# RaspPiPSOC.net
KiCad netlist of a schematic drawn in EAGLE
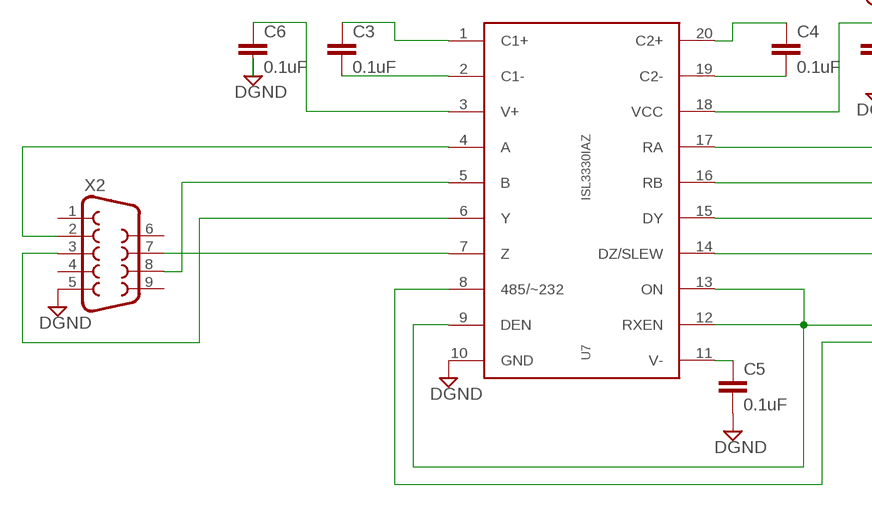
[diagram p0: schematic, sheet 1, part 1 of 2]
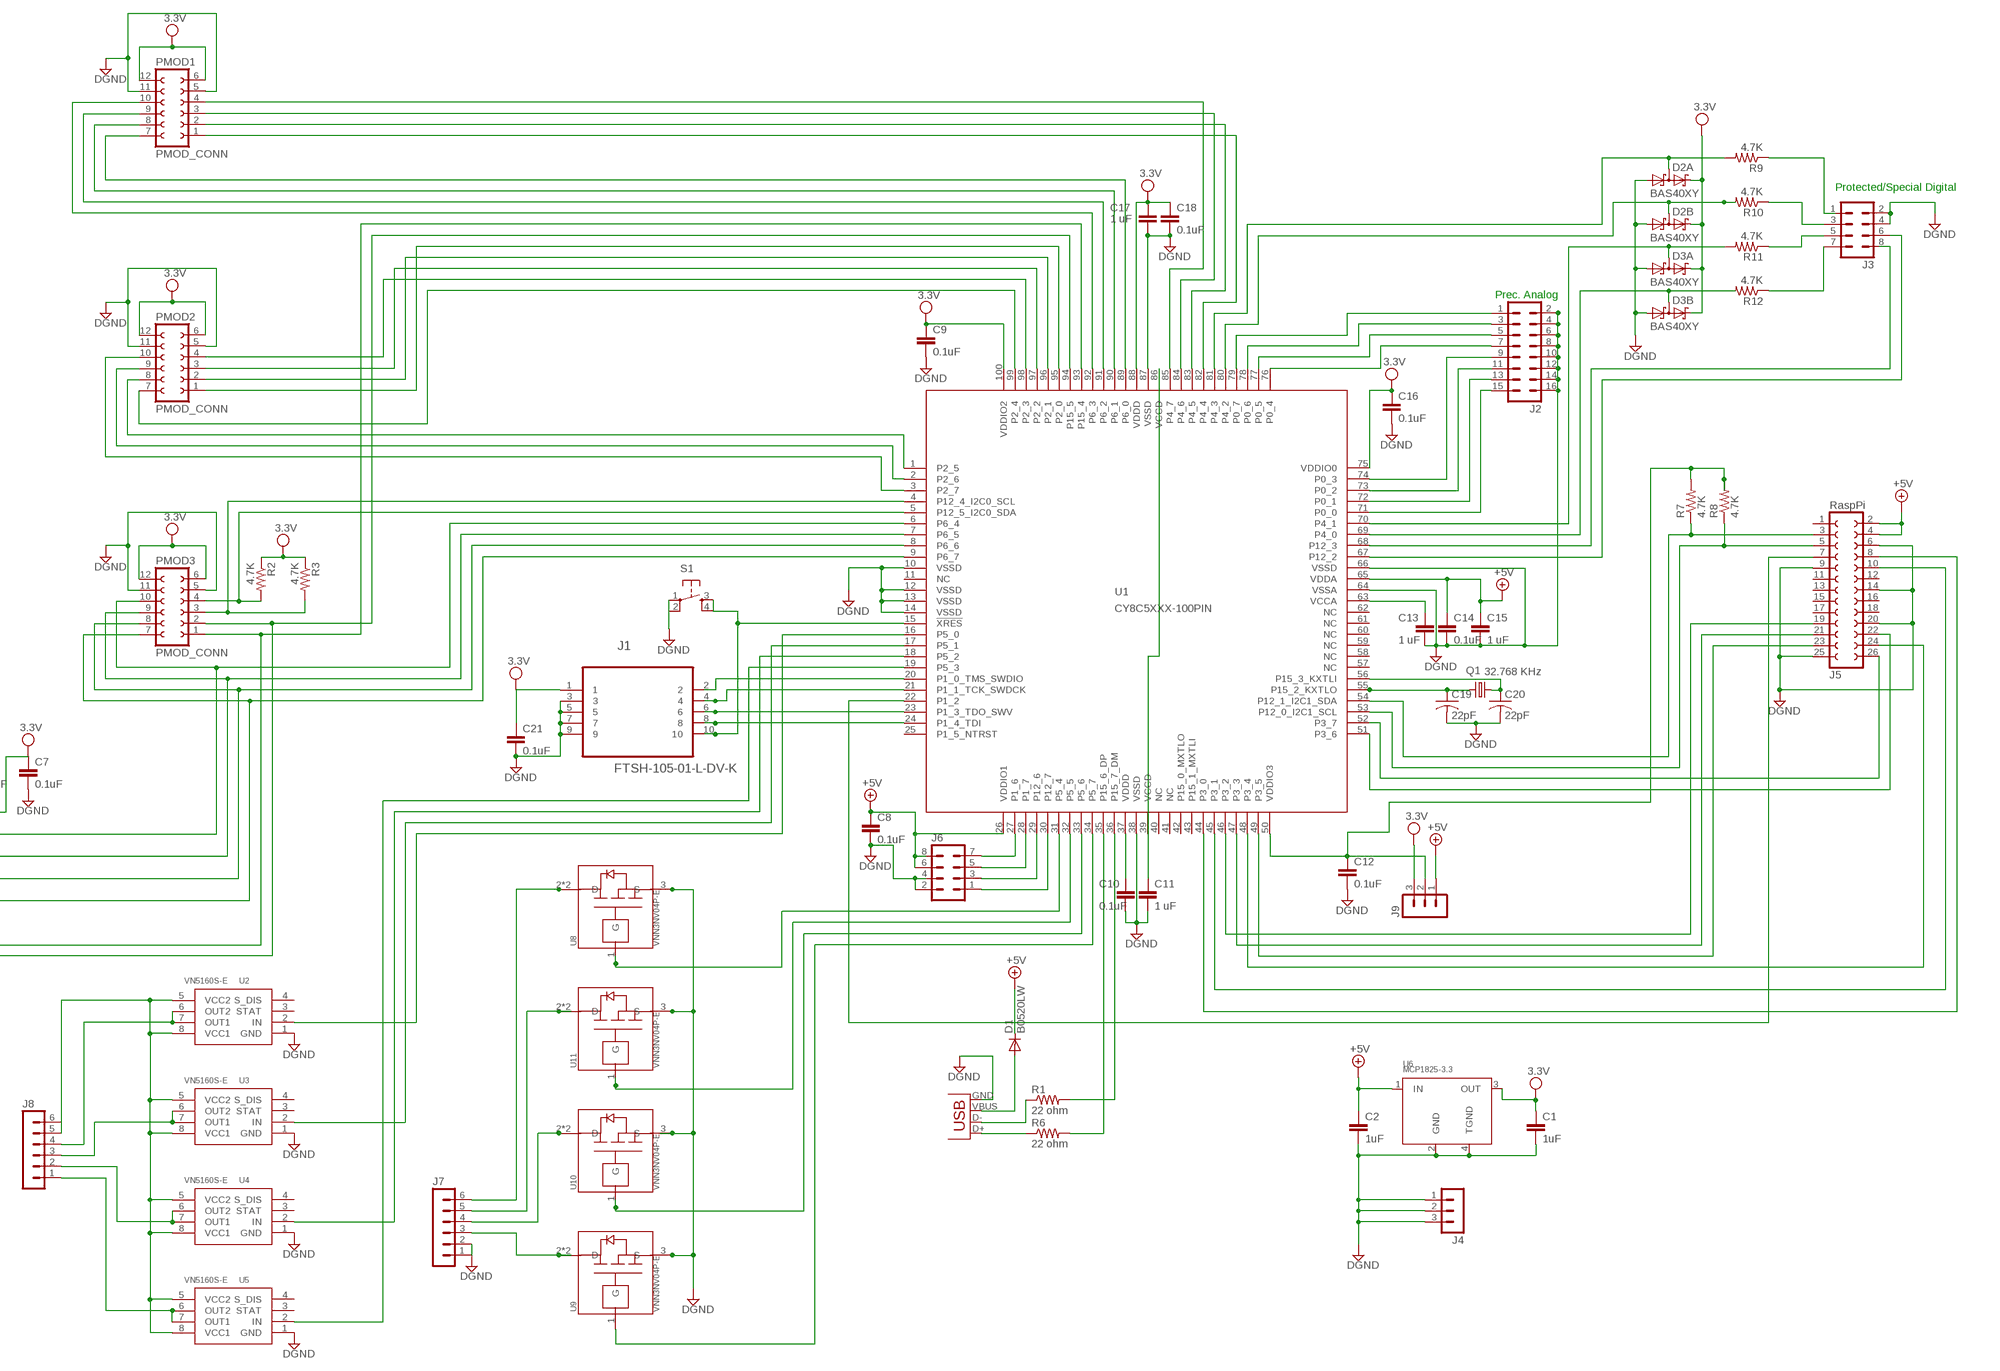
[diagram p1: schematic, sheet 1, part 2 of 2]

(export (version "E")
  (design (tool "Eeschema 10.0.6"))
  (components
    (comp (ref "C1")
      (value "1uF")
      (footprint "eagle-import:C0805")
      (libsource (lib "eagle-import") (part "resistor_C-EUC0805"))
    )
    (comp (ref "C2")
      (value "1uF")
      (footprint "eagle-import:C0805")
      (libsource (lib "eagle-import") (part "resistor_C-EUC0805"))
    )
    (comp (ref "C3")
      (value "0.1uF")
      (footprint "eagle-import:C0805")
      (libsource (lib "eagle-import") (part "C-EUC0805"))
    )
    (comp (ref "C4")
      (value "0.1uF")
      (footprint "eagle-import:C0805")
      (libsource (lib "eagle-import") (part "C-EUC0805"))
    )
    (comp (ref "C5")
      (value "0.1uF")
      (footprint "eagle-import:C0805")
      (libsource (lib "eagle-import") (part "C-EUC0805"))
    )
    (comp (ref "C6")
      (value "0.1uF")
      (footprint "eagle-import:C0805")
      (libsource (lib "eagle-import") (part "C-EUC0805"))
    )
    (comp (ref "C7")
      (value "0.1uF")
      (footprint "eagle-import:C0805")
      (libsource (lib "eagle-import") (part "C-EUC0805"))
    )
    (comp (ref "C8")
      (value "0.1uF")
      (footprint "eagle-import:C0805")
      (libsource (lib "eagle-import") (part "C-EUC0805"))
    )
    (comp (ref "C9")
      (value "0.1uF")
      (footprint "eagle-import:C0805")
      (libsource (lib "eagle-import") (part "C-EUC0805"))
    )
    (comp (ref "C10")
      (value "0.1uF")
      (footprint "eagle-import:C0805")
      (libsource (lib "eagle-import") (part "C-EUC0805"))
    )
    (comp (ref "C11")
      (value "1 uF")
      (footprint "eagle-import:C0805")
      (libsource (lib "eagle-import") (part "C-EUC0805"))
    )
    (comp (ref "C12")
      (value "0.1uF")
      (footprint "eagle-import:C0805")
      (libsource (lib "eagle-import") (part "C-EUC0805"))
    )
    (comp (ref "C13")
      (value "1 uF")
      (footprint "eagle-import:C0805")
      (libsource (lib "eagle-import") (part "C-EUC0805"))
    )
    (comp (ref "C14")
      (value "0.1uF")
      (footprint "eagle-import:C0805")
      (libsource (lib "eagle-import") (part "C-EUC0805"))
    )
    (comp (ref "C15")
      (value "1 uF")
      (footprint "eagle-import:C0805")
      (libsource (lib "eagle-import") (part "C-EUC0805"))
    )
    (comp (ref "C16")
      (value "0.1uF")
      (footprint "eagle-import:C0805")
      (libsource (lib "eagle-import") (part "C-EUC0805"))
    )
    (comp (ref "C17")
      (value "1 uF")
      (footprint "eagle-import:C0805")
      (libsource (lib "eagle-import") (part "C-EUC0805"))
    )
    (comp (ref "C18")
      (value "0.1uF")
      (footprint "eagle-import:C0805")
      (libsource (lib "eagle-import") (part "C-EUC0805"))
    )
    (comp (ref "C19")
      (value "22pF")
      (footprint "eagle-import:C0805")
      (libsource (lib "eagle-import") (part "C-USC0805"))
    )
    (comp (ref "C20")
      (value "22pF")
      (footprint "eagle-import:C0805")
      (libsource (lib "eagle-import") (part "C-USC0805"))
    )
    (comp (ref "C21")
      (value "0.1uF")
      (footprint "eagle-import:C0805")
      (libsource (lib "eagle-import") (part "C-EUC0805"))
    )
    (comp (ref "D1")
      (value "B0520LW")
      (footprint "eagle-import:SOD-123_MINI-SMA")
      (libsource (lib "eagle-import") (part "CGRM400-G3"))
    )
    (comp (ref "D2")
      (value "BAS40XY")
      (footprint "eagle-import:SOT363_PHILIPS")
      (libsource (lib "eagle-import") (part "BAS70XY"))
    )
    (comp (ref "D3")
      (value "BAS40XY")
      (footprint "eagle-import:SOT363_PHILIPS")
      (libsource (lib "eagle-import") (part "BAS70XY"))
    )
    (comp (ref "J1")
      (value "FTSH-105-01-L-DV-K")
      (footprint "eagle-import:SAMTEC_FTSH-105-01-L-DV-K")
      (libsource (lib "eagle-import") (part "FTSH-105-01-L-DV-K"))
    )
    (comp (ref "J2")
      (value "MA08-2")
      (footprint "eagle-import:MA08-2")
      (libsource (lib "eagle-import") (part "MA08-2"))
    )
    (comp (ref "J3")
      (value "MA04-2")
      (footprint "eagle-import:MA04-2")
      (libsource (lib "eagle-import") (part "MA04-2"))
    )
    (comp (ref "J4")
      (value "MA03-1")
      (footprint "eagle-import:MA03-1")
      (libsource (lib "eagle-import") (part "MA03-1"))
    )
    (comp (ref "J5")
      (value "RaspPi")
      (footprint "eagle-import:FE13-2")
      (libsource (lib "eagle-import") (part "FE13-2"))
    )
    (comp (ref "J6")
      (value "MA04-2")
      (footprint "eagle-import:MA04-2")
      (libsource (lib "eagle-import") (part "MA04-2"))
    )
    (comp (ref "J7")
      (value "MA06-1")
      (footprint "eagle-import:MA06-1")
      (libsource (lib "eagle-import") (part "MA06-1"))
    )
    (comp (ref "J8")
      (value "MA06-1")
      (footprint "eagle-import:MA06-1")
      (libsource (lib "eagle-import") (part "MA06-1"))
    )
    (comp (ref "J9")
      (value "MA03-1")
      (footprint "eagle-import:MA03-1")
      (libsource (lib "eagle-import") (part "MA03-1"))
    )
    (comp (ref "PMOD1")
      (value "PMOD_CONN")
      (footprint "eagle-import:PMOD_CONN")
      (libsource (lib "eagle-import") (part "PMOD_CONN"))
    )
    (comp (ref "PMOD2")
      (value "PMOD_CONN")
      (footprint "eagle-import:PMOD_CONN")
      (libsource (lib "eagle-import") (part "PMOD_CONN"))
    )
    (comp (ref "PMOD3")
      (value "PMOD_CONN")
      (footprint "eagle-import:PMOD_CONN")
      (libsource (lib "eagle-import") (part "PMOD_CONN"))
    )
    (comp (ref "Q1")
      (value "32.768 KHz")
      (footprint "eagle-import:TC26H")
      (libsource (lib "eagle-import") (part "CRYSTALTC26H"))
    )
    (comp (ref "R1")
      (value "22 ohm")
      (footprint "eagle-import:R0805")
      (libsource (lib "eagle-import") (part "R-US_R0805"))
    )
    (comp (ref "R2")
      (value "4.7K")
      (footprint "eagle-import:R0805")
      (libsource (lib "eagle-import") (part "R-US_R0805"))
    )
    (comp (ref "R3")
      (value "4.7K")
      (footprint "eagle-import:R0805")
      (libsource (lib "eagle-import") (part "R-US_R0805"))
    )
    (comp (ref "R6")
      (value "22 ohm")
      (footprint "eagle-import:R0805")
      (libsource (lib "eagle-import") (part "R-US_R0805"))
    )
    (comp (ref "R7")
      (value "4.7K")
      (footprint "eagle-import:R0805")
      (libsource (lib "eagle-import") (part "R-US_R0805"))
    )
    (comp (ref "R8")
      (value "4.7K")
      (footprint "eagle-import:R0805")
      (libsource (lib "eagle-import") (part "R-US_R0805"))
    )
    (comp (ref "R9")
      (value "4.7K")
      (footprint "eagle-import:R0805")
      (libsource (lib "eagle-import") (part "R-US_R0805"))
    )
    (comp (ref "R10")
      (value "4.7K")
      (footprint "eagle-import:R0805")
      (libsource (lib "eagle-import") (part "R-US_R0805"))
    )
    (comp (ref "R11")
      (value "4.7K")
      (footprint "eagle-import:R0805")
      (libsource (lib "eagle-import") (part "R-US_R0805"))
    )
    (comp (ref "R12")
      (value "4.7K")
      (footprint "eagle-import:R0805")
      (libsource (lib "eagle-import") (part "R-US_R0805"))
    )
    (comp (ref "S1")
      (value "TAC_SWITCHSMD")
      (footprint "eagle-import:TACTILE_SWITCH_SMD")
      (libsource (lib "eagle-import") (part "TAC_SWITCHSMD"))
    )
    (comp (ref "U1")
      (value "CY8C5XXX-100PIN")
      (footprint "eagle-import:TQFP-14X14-100")
      (fields (field (name "MPN") "CY8C5588AXI-060"))
      (libsource (lib "eagle-import") (part "CY8C5XXX-100PIN"))
    )
    (comp (ref "U2")
      (value "VN5160S-E")
      (footprint "eagle-import:SOIC8")
      (libsource (lib "eagle-import") (part "VN5160S-E"))
    )
    (comp (ref "U3")
      (value "VN5160S-E")
      (footprint "eagle-import:SOIC8")
      (libsource (lib "eagle-import") (part "VN5160S-E"))
    )
    (comp (ref "U4")
      (value "VN5160S-E")
      (footprint "eagle-import:SOIC8")
      (libsource (lib "eagle-import") (part "VN5160S-E"))
    )
    (comp (ref "U5")
      (value "VN5160S-E")
      (footprint "eagle-import:SOIC8")
      (libsource (lib "eagle-import") (part "VN5160S-E"))
    )
    (comp (ref "U6")
      (value "MCP1825-3.3")
      (footprint "eagle-import:SOT223")
      (libsource (lib "eagle-import") (part "TC1262"))
    )
    (comp (ref "U7")
      (value "ISL3330IAZ")
      (footprint "eagle-import:SSOP20")
      (libsource (lib "eagle-import") (part "ISL3330IAZ"))
    )
    (comp (ref "U8")
      (value "VNN3NV04P-E")
      (footprint "eagle-import:SOT223")
      (libsource (lib "eagle-import") (part "VNN3NV04P-E"))
    )
    (comp (ref "U9")
      (value "VNN3NV04P-E")
      (footprint "eagle-import:SOT223")
      (libsource (lib "eagle-import") (part "VNN3NV04P-E"))
    )
    (comp (ref "U10")
      (value "VNN3NV04P-E")
      (footprint "eagle-import:SOT223")
      (libsource (lib "eagle-import") (part "VNN3NV04P-E"))
    )
    (comp (ref "U11")
      (value "VNN3NV04P-E")
      (footprint "eagle-import:SOT223")
      (libsource (lib "eagle-import") (part "VNN3NV04P-E"))
    )
    (comp (ref "X1")
      (value "USBSMD")
      (footprint "eagle-import:USB-MINIB")
      (libsource (lib "eagle-import") (part "USBSMD"))
    )
    (comp (ref "X2")
      (value "DB9")
      (footprint "eagle-import:DB9")
      (libsource (lib "eagle-import") (part "DB9"))
    )
  )
  (nets
    (net (code "1") (name "+5V") (class "Default")
      (node (ref "C14") (pin "1") (pinfunction "1_1") (pintype "passive"))
      (node (ref "C15") (pin "1") (pinfunction "1_1") (pintype "passive"))
      (node (ref "C2") (pin "1") (pinfunction "1_1") (pintype "passive"))
      (node (ref "C8") (pin "1") (pinfunction "1_1") (pintype "passive"))
      (node (ref "D1") (pin "C") (pinfunction "C_C") (pintype "passive"))
      (node (ref "J5") (pin "2") (pinfunction "2_2") (pintype "passive"))
      (node (ref "J5") (pin "4") (pinfunction "4_4") (pintype "passive"))
      (node (ref "J6") (pin "6") (pinfunction "6_6") (pintype "passive"))
      (node (ref "J6") (pin "8") (pinfunction "8_8") (pintype "passive"))
      (node (ref "J9") (pin "1") (pinfunction "1_1") (pintype "passive"))
      (node (ref "U1") (pin "26") (pinfunction "VDDIO1_26") (pintype "passive"))
      (node (ref "U1") (pin "65") (pinfunction "VDDA_65") (pintype "passive"))
      (node (ref "U6") (pin "1") (pinfunction "IN_1") (pintype "bidirectional"))
    )
    (net (code "2") (name "3.3V") (class "Default")
      (node (ref "C1") (pin "1") (pinfunction "1_1") (pintype "passive"))
      (node (ref "C16") (pin "1") (pinfunction "1_1") (pintype "passive"))
      (node (ref "C17") (pin "1") (pinfunction "1_1") (pintype "passive"))
      (node (ref "C18") (pin "1") (pinfunction "1_1") (pintype "passive"))
      (node (ref "C21") (pin "1") (pinfunction "1_1") (pintype "passive"))
      (node (ref "C7") (pin "1") (pinfunction "1_1") (pintype "passive"))
      (node (ref "C9") (pin "1") (pinfunction "1_1") (pintype "passive"))
      (node (ref "D2") (pin "2") (pinfunction "C2_2") (pintype "passive"))
      (node (ref "D2") (pin "5") (pinfunction "C2_5") (pintype "passive"))
      (node (ref "D3") (pin "2") (pinfunction "C2_2") (pintype "passive"))
      (node (ref "D3") (pin "5") (pinfunction "C2_5") (pintype "passive"))
      (node (ref "J1") (pin "1") (pinfunction "1_1") (pintype "passive"))
      (node (ref "J9") (pin "3") (pinfunction "3_3") (pintype "passive"))
      (node (ref "PMOD1") (pin "12") (pinfunction "12_12") (pintype "passive"))
      (node (ref "PMOD1") (pin "6") (pinfunction "6_6") (pintype "passive"))
      (node (ref "PMOD2") (pin "12") (pinfunction "12_12") (pintype "passive"))
      (node (ref "PMOD2") (pin "6") (pinfunction "6_6") (pintype "passive"))
      (node (ref "PMOD3") (pin "12") (pinfunction "12_12") (pintype "passive"))
      (node (ref "PMOD3") (pin "6") (pinfunction "6_6") (pintype "passive"))
      (node (ref "R2") (pin "1") (pinfunction "1_1") (pintype "passive"))
      (node (ref "R3") (pin "1") (pinfunction "1_1") (pintype "passive"))
      (node (ref "U1") (pin "100") (pinfunction "VDDIO2_100") (pintype "passive"))
      (node (ref "U1") (pin "75") (pinfunction "VDDIO0_75") (pintype "passive"))
      (node (ref "U1") (pin "88") (pinfunction "VDDD_88") (pintype "passive"))
      (node (ref "U6") (pin "3") (pinfunction "OUT_3") (pintype "bidirectional"))
      (node (ref "U7") (pin "18") (pinfunction "VCC_18") (pintype "power_in"))
    )
    (net (code "3") (name "DGND") (class "Default")
      (node (ref "C1") (pin "2") (pinfunction "2_2") (pintype "passive"))
      (node (ref "C10") (pin "2") (pinfunction "2_2") (pintype "passive"))
      (node (ref "C11") (pin "2") (pinfunction "2_2") (pintype "passive"))
      (node (ref "C12") (pin "2") (pinfunction "2_2") (pintype "passive"))
      (node (ref "C13") (pin "2") (pinfunction "2_2") (pintype "passive"))
      (node (ref "C14") (pin "2") (pinfunction "2_2") (pintype "passive"))
      (node (ref "C15") (pin "2") (pinfunction "2_2") (pintype "passive"))
      (node (ref "C16") (pin "2") (pinfunction "2_2") (pintype "passive"))
      (node (ref "C17") (pin "2") (pinfunction "2_2") (pintype "passive"))
      (node (ref "C18") (pin "2") (pinfunction "2_2") (pintype "passive"))
      (node (ref "C19") (pin "2") (pinfunction "2_2") (pintype "passive"))
      (node (ref "C2") (pin "2") (pinfunction "2_2") (pintype "passive"))
      (node (ref "C20") (pin "2") (pinfunction "2_2") (pintype "passive"))
      (node (ref "C21") (pin "2") (pinfunction "2_2") (pintype "passive"))
      (node (ref "C5") (pin "2") (pinfunction "2_2") (pintype "passive"))
      (node (ref "C6") (pin "2") (pinfunction "2_2") (pintype "passive"))
      (node (ref "C7") (pin "2") (pinfunction "2_2") (pintype "passive"))
      (node (ref "C8") (pin "2") (pinfunction "2_2") (pintype "passive"))
      (node (ref "C9") (pin "2") (pinfunction "2_2") (pintype "passive"))
      (node (ref "D2") (pin "1") (pinfunction "A1_1") (pintype "passive"))
      (node (ref "D2") (pin "4") (pinfunction "A1_4") (pintype "passive"))
      (node (ref "D3") (pin "1") (pinfunction "A1_1") (pintype "passive"))
      (node (ref "D3") (pin "4") (pinfunction "A1_4") (pintype "passive"))
      (node (ref "J1") (pin "3") (pinfunction "3_3") (pintype "passive"))
      (node (ref "J1") (pin "5") (pinfunction "5_5") (pintype "passive"))
      (node (ref "J1") (pin "7") (pinfunction "7_7") (pintype "passive"))
      (node (ref "J1") (pin "9") (pinfunction "9_9") (pintype "passive"))
      (node (ref "J2") (pin "10") (pinfunction "10_10") (pintype "passive"))
      (node (ref "J2") (pin "12") (pinfunction "12_12") (pintype "passive"))
      (node (ref "J2") (pin "14") (pinfunction "14_14") (pintype "passive"))
      (node (ref "J2") (pin "16") (pinfunction "16_16") (pintype "passive"))
      (node (ref "J2") (pin "2") (pinfunction "2_2") (pintype "passive"))
      (node (ref "J2") (pin "4") (pinfunction "4_4") (pintype "passive"))
      (node (ref "J2") (pin "6") (pinfunction "6_6") (pintype "passive"))
      (node (ref "J2") (pin "8") (pinfunction "8_8") (pintype "passive"))
      (node (ref "J3") (pin "2") (pinfunction "2_2") (pintype "passive"))
      (node (ref "J3") (pin "4") (pinfunction "4_4") (pintype "passive"))
      (node (ref "J4") (pin "1") (pinfunction "1_1") (pintype "passive"))
      (node (ref "J4") (pin "2") (pinfunction "2_2") (pintype "passive"))
      (node (ref "J4") (pin "3") (pinfunction "3_3") (pintype "passive"))
      (node (ref "J5") (pin "14") (pinfunction "14_14") (pintype "passive"))
      (node (ref "J5") (pin "20") (pinfunction "20_20") (pintype "passive"))
      (node (ref "J5") (pin "25") (pinfunction "25_25") (pintype "passive"))
      (node (ref "J5") (pin "6") (pinfunction "6_6") (pintype "passive"))
      (node (ref "J5") (pin "9") (pinfunction "9_9") (pintype "passive"))
      (node (ref "J6") (pin "2") (pinfunction "2_2") (pintype "passive"))
      (node (ref "J6") (pin "4") (pinfunction "4_4") (pintype "passive"))
      (node (ref "J7") (pin "1") (pinfunction "1_1") (pintype "passive"))
      (node (ref "J7") (pin "2") (pinfunction "2_2") (pintype "passive"))
      (node (ref "PMOD1") (pin "11") (pinfunction "11_11") (pintype "passive"))
      (node (ref "PMOD1") (pin "5") (pinfunction "5_5") (pintype "passive"))
      (node (ref "PMOD2") (pin "11") (pinfunction "11_11") (pintype "passive"))
      (node (ref "PMOD2") (pin "5") (pinfunction "5_5") (pintype "passive"))
      (node (ref "PMOD3") (pin "11") (pinfunction "11_11") (pintype "passive"))
      (node (ref "PMOD3") (pin "5") (pinfunction "5_5") (pintype "passive"))
      (node (ref "S1") (pin "1") (pinfunction "1_1") (pintype "passive"))
      (node (ref "S1") (pin "2") (pinfunction "2_2") (pintype "passive"))
      (node (ref "U1") (pin "10") (pinfunction "VSSD_10") (pintype "passive"))
      (node (ref "U1") (pin "12") (pinfunction "VSSD_12") (pintype "passive"))
      (node (ref "U1") (pin "13") (pinfunction "VSSD_13") (pintype "passive"))
      (node (ref "U1") (pin "14") (pinfunction "VSSD_14") (pintype "passive"))
      (node (ref "U1") (pin "38") (pinfunction "VSSD_38") (pintype "passive"))
      (node (ref "U1") (pin "64") (pinfunction "VSSA_64") (pintype "passive"))
      (node (ref "U1") (pin "66") (pinfunction "VSSD_66") (pintype "passive"))
      (node (ref "U1") (pin "87") (pinfunction "VSSD_87") (pintype "passive"))
      (node (ref "U10") (pin "3") (pinfunction "S_3") (pintype "bidirectional"))
      (node (ref "U11") (pin "3") (pinfunction "S_3") (pintype "bidirectional"))
      (node (ref "U2") (pin "1") (pinfunction "GND_1") (pintype "power_in"))
      (node (ref "U3") (pin "1") (pinfunction "GND_1") (pintype "power_in"))
      (node (ref "U4") (pin "1") (pinfunction "GND_1") (pintype "power_in"))
      (node (ref "U5") (pin "1") (pinfunction "GND_1") (pintype "power_in"))
      (node (ref "U6") (pin "2") (pinfunction "GND_2") (pintype "bidirectional"))
      (node (ref "U6") (pin "4") (pinfunction "TGND_4") (pintype "bidirectional"))
      (node (ref "U7") (pin "10") (pinfunction "GND_10") (pintype "power_in"))
      (node (ref "U8") (pin "3") (pinfunction "S_3") (pintype "bidirectional"))
      (node (ref "U9") (pin "3") (pinfunction "S_3") (pintype "bidirectional"))
      (node (ref "X1") (pin "GND") (pinfunction "GND_GND") (pintype "bidirectional"))
      (node (ref "X2") (pin "5") (pinfunction "5_5") (pintype "passive"))
    )
    (net (code "4") (name "Net-(C10-Pad1)") (class "Default")
      (node (ref "C10") (pin "1") (pinfunction "1_1") (pintype "passive"))
      (node (ref "U1") (pin "37") (pinfunction "VDDD_37") (pintype "passive"))
    )
    (net (code "5") (name "Net-(C11-Pad1)") (class "Default")
      (node (ref "C11") (pin "1") (pinfunction "1_1") (pintype "passive"))
      (node (ref "U1") (pin "39") (pinfunction "VCCD_39") (pintype "passive"))
      (node (ref "U1") (pin "86") (pinfunction "VCCD_86") (pintype "passive"))
    )
    (net (code "6") (name "Net-(D1-PadA)") (class "Default")
      (node (ref "D1") (pin "A") (pinfunction "A_A") (pintype "passive"))
      (node (ref "X1") (pin "VBUS") (pinfunction "VBUS_VBUS") (pintype "bidirectional"))
    )
    (net (code "7") (name "Net-(D2A-C1A2)") (class "Default")
      (node (ref "D2") (pin "6") (pinfunction "C1A2_6") (pintype "passive"))
      (node (ref "R9") (pin "2") (pinfunction "2_2") (pintype "passive"))
      (node (ref "U1") (pin "81") (pinfunction "P4_3_81") (pintype "passive"))
    )
    (net (code "8") (name "Net-(D2B-C1A2)") (class "Default")
      (node (ref "D2") (pin "3") (pinfunction "C1A2_3") (pintype "passive"))
      (node (ref "R10") (pin "2") (pinfunction "2_2") (pintype "passive"))
      (node (ref "U1") (pin "80") (pinfunction "P4_2_80") (pintype "passive"))
    )
    (net (code "9") (name "Net-(D3A-C1A2)") (class "Default")
      (node (ref "D3") (pin "6") (pinfunction "C1A2_6") (pintype "passive"))
      (node (ref "R11") (pin "2") (pinfunction "2_2") (pintype "passive"))
      (node (ref "U1") (pin "70") (pinfunction "P4_1_70") (pintype "passive"))
    )
    (net (code "10") (name "Net-(D3B-C1A2)") (class "Default")
      (node (ref "D3") (pin "3") (pinfunction "C1A2_3") (pintype "passive"))
      (node (ref "R12") (pin "2") (pinfunction "2_2") (pintype "passive"))
      (node (ref "U1") (pin "69") (pinfunction "P4_0_69") (pintype "passive"))
    )
    (net (code "11") (name "Net-(J3-Pad1)") (class "Default")
      (node (ref "J3") (pin "1") (pinfunction "1_1") (pintype "passive"))
      (node (ref "R9") (pin "1") (pinfunction "1_1") (pintype "passive"))
    )
    (net (code "12") (name "Net-(J3-Pad3)") (class "Default")
      (node (ref "J3") (pin "3") (pinfunction "3_3") (pintype "passive"))
      (node (ref "R10") (pin "1") (pinfunction "1_1") (pintype "passive"))
    )
    (net (code "13") (name "Net-(J3-Pad5)") (class "Default")
      (node (ref "J3") (pin "5") (pinfunction "5_5") (pintype "passive"))
      (node (ref "R11") (pin "1") (pinfunction "1_1") (pintype "passive"))
    )
    (net (code "14") (name "Net-(J3-Pad7)") (class "Default")
      (node (ref "J3") (pin "7") (pinfunction "7_7") (pintype "passive"))
      (node (ref "R12") (pin "1") (pinfunction "1_1") (pintype "passive"))
    )
    (net (code "15") (name "Net-(J7-Pad3)") (class "Default")
      (node (ref "J7") (pin "3") (pinfunction "3_3") (pintype "passive"))
      (node (ref "U9") (pin "2") (pinfunction "D_2") (pintype "bidirectional"))
      (node (ref "U9") (pin "4") (pinfunction "D_4") (pintype "bidirectional"))
    )
    (net (code "16") (name "Net-(J7-Pad4)") (class "Default")
      (node (ref "J7") (pin "4") (pinfunction "4_4") (pintype "passive"))
      (node (ref "U10") (pin "2") (pinfunction "D_2") (pintype "bidirectional"))
      (node (ref "U10") (pin "4") (pinfunction "D_4") (pintype "bidirectional"))
    )
    (net (code "17") (name "Net-(J7-Pad5)") (class "Default")
      (node (ref "J7") (pin "5") (pinfunction "5_5") (pintype "passive"))
      (node (ref "U11") (pin "2") (pinfunction "D_2") (pintype "bidirectional"))
      (node (ref "U11") (pin "4") (pinfunction "D_4") (pintype "bidirectional"))
    )
    (net (code "18") (name "Net-(J7-Pad6)") (class "Default")
      (node (ref "J7") (pin "6") (pinfunction "6_6") (pintype "passive"))
      (node (ref "U8") (pin "2") (pinfunction "D_2") (pintype "bidirectional"))
      (node (ref "U8") (pin "4") (pinfunction "D_4") (pintype "bidirectional"))
    )
    (net (code "19") (name "Net-(R1-Pad1)") (class "Default")
      (node (ref "R1") (pin "1") (pinfunction "1_1") (pintype "passive"))
      (node (ref "X1") (pin "D-") (pinfunction "D-_D-") (pintype "bidirectional"))
    )
    (net (code "20") (name "Net-(R6-Pad1)") (class "Default")
      (node (ref "R6") (pin "1") (pinfunction "1_1") (pintype "passive"))
      (node (ref "X1") (pin "D+") (pinfunction "D+_D+") (pintype "bidirectional"))
    )
    (net (code "21") (name "Net-(U1-P0_0)") (class "Default")
      (node (ref "J2") (pin "15") (pinfunction "15_15") (pintype "passive"))
      (node (ref "U1") (pin "71") (pinfunction "P0_0_71") (pintype "passive"))
    )
    (net (code "22") (name "Net-(U1-P0_1)") (class "Default")
      (node (ref "J2") (pin "13") (pinfunction "13_13") (pintype "passive"))
      (node (ref "U1") (pin "72") (pinfunction "P0_1_72") (pintype "passive"))
    )
    (net (code "23") (name "Net-(U1-P0_2)") (class "Default")
      (node (ref "J2") (pin "11") (pinfunction "11_11") (pintype "passive"))
      (node (ref "U1") (pin "73") (pinfunction "P0_2_73") (pintype "passive"))
    )
    (net (code "24") (name "Net-(U1-P0_3)") (class "Default")
      (node (ref "J2") (pin "9") (pinfunction "9_9") (pintype "passive"))
      (node (ref "U1") (pin "74") (pinfunction "P0_3_74") (pintype "passive"))
    )
    (net (code "25") (name "Net-(U1-P0_4)") (class "Default")
      (node (ref "J2") (pin "7") (pinfunction "7_7") (pintype "passive"))
      (node (ref "U1") (pin "76") (pinfunction "P0_4_76") (pintype "passive"))
    )
    (net (code "26") (name "Net-(U1-P0_5)") (class "Default")
      (node (ref "J2") (pin "5") (pinfunction "5_5") (pintype "passive"))
      (node (ref "U1") (pin "77") (pinfunction "P0_5_77") (pintype "passive"))
    )
    (net (code "27") (name "Net-(U1-P0_6)") (class "Default")
      (node (ref "J2") (pin "3") (pinfunction "3_3") (pintype "passive"))
      (node (ref "U1") (pin "78") (pinfunction "P0_6_78") (pintype "passive"))
    )
    (net (code "28") (name "Net-(U1-P0_7)") (class "Default")
      (node (ref "J2") (pin "1") (pinfunction "1_1") (pintype "passive"))
      (node (ref "U1") (pin "79") (pinfunction "P0_7_79") (pintype "passive"))
    )
    (net (code "29") (name "Net-(U1-P1_0_TMS_SWDIO)") (class "Default")
      (node (ref "J1") (pin "2") (pinfunction "2_2") (pintype "passive"))
      (node (ref "U1") (pin "20") (pinfunction "P1_0_TMS_SWDIO_20") (pintype "passive"))
    )
    (net (code "30") (name "Net-(U1-P1_1_TCK_SWDCK)") (class "Default")
      (node (ref "J1") (pin "4") (pinfunction "4_4") (pintype "passive"))
      (node (ref "U1") (pin "21") (pinfunction "P1_1_TCK_SWDCK_21") (pintype "passive"))
    )
    (net (code "31") (name "Net-(U1-P1_2)") (class "Default")
      (node (ref "J5") (pin "7") (pinfunction "7_7") (pintype "passive"))
      (node (ref "U1") (pin "22") (pinfunction "P1_2_22") (pintype "passive"))
    )
    (net (code "32") (name "Net-(U1-P1_3_TDO_SWV)") (class "Default")
      (node (ref "J1") (pin "6") (pinfunction "6_6") (pintype "passive"))
      (node (ref "U1") (pin "23") (pinfunction "P1_3_TDO_SWV_23") (pintype "passive"))
    )
    (net (code "33") (name "Net-(U1-P1_4_TDI)") (class "Default")
      (node (ref "J1") (pin "8") (pinfunction "8_8") (pintype "passive"))
      (node (ref "U1") (pin "24") (pinfunction "P1_4_TDI_24") (pintype "passive"))
    )
    (net (code "34") (name "Net-(U1-P1_6)") (class "Default")
      (node (ref "J6") (pin "7") (pinfunction "7_7") (pintype "passive"))
      (node (ref "U1") (pin "27") (pinfunction "P1_6_27") (pintype "passive"))
    )
    (net (code "35") (name "Net-(U1-P1_7)") (class "Default")
      (node (ref "J6") (pin "5") (pinfunction "5_5") (pintype "passive"))
      (node (ref "U1") (pin "28") (pinfunction "P1_7_28") (pintype "passive"))
    )
    (net (code "36") (name "Net-(U1-P2_0)") (class "Default")
      (node (ref "PMOD2") (pin "1") (pinfunction "1_1") (pintype "passive"))
      (node (ref "U1") (pin "95") (pinfunction "P2_0_95") (pintype "passive"))
    )
    (net (code "37") (name "Net-(U1-P2_1)") (class "Default")
      (node (ref "PMOD2") (pin "2") (pinfunction "2_2") (pintype "passive"))
      (node (ref "U1") (pin "96") (pinfunction "P2_1_96") (pintype "passive"))
    )
    (net (code "38") (name "Net-(U1-P2_2)") (class "Default")
      (node (ref "PMOD2") (pin "3") (pinfunction "3_3") (pintype "passive"))
      (node (ref "U1") (pin "97") (pinfunction "P2_2_97") (pintype "passive"))
    )
    (net (code "39") (name "Net-(U1-P2_3)") (class "Default")
      (node (ref "PMOD2") (pin "4") (pinfunction "4_4") (pintype "passive"))
      (node (ref "U1") (pin "98") (pinfunction "P2_3_98") (pintype "passive"))
    )
    (net (code "40") (name "Net-(U1-P2_4)") (class "Default")
      (node (ref "PMOD2") (pin "7") (pinfunction "7_7") (pintype "passive"))
      (node (ref "U1") (pin "99") (pinfunction "P2_4_99") (pintype "passive"))
    )
    (net (code "41") (name "Net-(U1-P2_5)") (class "Default")
      (node (ref "PMOD2") (pin "8") (pinfunction "8_8") (pintype "passive"))
      (node (ref "U1") (pin "1") (pinfunction "P2_5_1") (pintype "passive"))
    )
    (net (code "42") (name "Net-(U1-P2_6)") (class "Default")
      (node (ref "PMOD2") (pin "9") (pinfunction "9_9") (pintype "passive"))
      (node (ref "U1") (pin "2") (pinfunction "P2_6_2") (pintype "passive"))
    )
    (net (code "43") (name "Net-(U1-P2_7)") (class "Default")
      (node (ref "PMOD2") (pin "10") (pinfunction "10_10") (pintype "passive"))
      (node (ref "U1") (pin "3") (pinfunction "P2_7_3") (pintype "passive"))
    )
    (net (code "44") (name "Net-(U1-P3_0)") (class "Default")
      (node (ref "J5") (pin "8") (pinfunction "8_8") (pintype "passive"))
      (node (ref "U1") (pin "44") (pinfunction "P3_0_44") (pintype "passive"))
    )
    (net (code "45") (name "Net-(U1-P3_1)") (class "Default")
      (node (ref "J5") (pin "10") (pinfunction "10_10") (pintype "passive"))
      (node (ref "U1") (pin "45") (pinfunction "P3_1_45") (pintype "passive"))
    )
    (net (code "46") (name "Net-(U1-P3_2)") (class "Default")
      (node (ref "J5") (pin "19") (pinfunction "19_19") (pintype "passive"))
      (node (ref "U1") (pin "46") (pinfunction "P3_2_46") (pintype "passive"))
    )
    (net (code "47") (name "Net-(U1-P3_3)") (class "Default")
      (node (ref "J5") (pin "21") (pinfunction "21_21") (pintype "passive"))
      (node (ref "U1") (pin "47") (pinfunction "P3_3_47") (pintype "passive"))
    )
    (net (code "48") (name "Net-(U1-P3_4)") (class "Default")
      (node (ref "J5") (pin "24") (pinfunction "24_24") (pintype "passive"))
      (node (ref "U1") (pin "48") (pinfunction "P3_4_48") (pintype "passive"))
    )
    (net (code "49") (name "Net-(U1-P3_5)") (class "Default")
      (node (ref "J5") (pin "23") (pinfunction "23_23") (pintype "passive"))
      (node (ref "U1") (pin "49") (pinfunction "P3_5_49") (pintype "passive"))
    )
    (net (code "50") (name "Net-(U1-P3_6)") (class "Default")
      (node (ref "J5") (pin "22") (pinfunction "22_22") (pintype "passive"))
      (node (ref "U1") (pin "51") (pinfunction "P3_6_51") (pintype "passive"))
    )
    (net (code "51") (name "Net-(U1-P3_7)") (class "Default")
      (node (ref "J5") (pin "26") (pinfunction "26_26") (pintype "passive"))
      (node (ref "U1") (pin "52") (pinfunction "P3_7_52") (pintype "passive"))
    )
    (net (code "52") (name "Net-(U1-P4_4)") (class "Default")
      (node (ref "PMOD1") (pin "1") (pinfunction "1_1") (pintype "passive"))
      (node (ref "U1") (pin "82") (pinfunction "P4_4_82") (pintype "passive"))
    )
    (net (code "53") (name "Net-(U1-P4_5)") (class "Default")
      (node (ref "PMOD1") (pin "2") (pinfunction "2_2") (pintype "passive"))
      (node (ref "U1") (pin "83") (pinfunction "P4_5_83") (pintype "passive"))
    )
    (net (code "54") (name "Net-(U1-P4_6)") (class "Default")
      (node (ref "PMOD1") (pin "3") (pinfunction "3_3") (pintype "passive"))
      (node (ref "U1") (pin "84") (pinfunction "P4_6_84") (pintype "passive"))
    )
    (net (code "55") (name "Net-(U1-P4_7)") (class "Default")
      (node (ref "PMOD1") (pin "4") (pinfunction "4_4") (pintype "passive"))
      (node (ref "U1") (pin "85") (pinfunction "P4_7_85") (pintype "passive"))
    )
    (net (code "56") (name "Net-(U1-P5_0)") (class "Default")
      (node (ref "U1") (pin "16") (pinfunction "P5_0_16") (pintype "passive"))
      (node (ref "U2") (pin "2") (pinfunction "IN_2") (pintype "input"))
    )
    (net (code "57") (name "Net-(U1-P5_1)") (class "Default")
      (node (ref "U1") (pin "17") (pinfunction "P5_1_17") (pintype "passive"))
      (node (ref "U3") (pin "2") (pinfunction "IN_2") (pintype "input"))
    )
    (net (code "58") (name "Net-(U1-P5_2)") (class "Default")
      (node (ref "U1") (pin "18") (pinfunction "P5_2_18") (pintype "passive"))
      (node (ref "U4") (pin "2") (pinfunction "IN_2") (pintype "input"))
    )
    (net (code "59") (name "Net-(U1-P5_3)") (class "Default")
      (node (ref "U1") (pin "19") (pinfunction "P5_3_19") (pintype "passive"))
      (node (ref "U5") (pin "2") (pinfunction "IN_2") (pintype "input"))
    )
    (net (code "60") (name "Net-(U1-P5_4)") (class "Default")
      (node (ref "U1") (pin "31") (pinfunction "P5_4_31") (pintype "passive"))
      (node (ref "U8") (pin "1") (pinfunction "G_1") (pintype "bidirectional"))
    )
    (net (code "61") (name "Net-(U1-P5_5)") (class "Default")
      (node (ref "U1") (pin "32") (pinfunction "P5_5_32") (pintype "passive"))
      (node (ref "U11") (pin "1") (pinfunction "G_1") (pintype "bidirectional"))
    )
    (net (code "62") (name "Net-(U1-P5_6)") (class "Default")
      (node (ref "U1") (pin "33") (pinfunction "P5_6_33") (pintype "passive"))
      (node (ref "U10") (pin "1") (pinfunction "G_1") (pintype "bidirectional"))
    )
    (net (code "63") (name "Net-(U1-P5_7)") (class "Default")
      (node (ref "U1") (pin "34") (pinfunction "P5_7_34") (pintype "passive"))
      (node (ref "U9") (pin "1") (pinfunction "G_1") (pintype "bidirectional"))
    )
    (net (code "64") (name "Net-(U1-P6_0)") (class "Default")
      (node (ref "PMOD1") (pin "7") (pinfunction "7_7") (pintype "passive"))
      (node (ref "U1") (pin "89") (pinfunction "P6_0_89") (pintype "passive"))
    )
    (net (code "65") (name "Net-(U1-P6_1)") (class "Default")
      (node (ref "PMOD1") (pin "8") (pinfunction "8_8") (pintype "passive"))
      (node (ref "U1") (pin "90") (pinfunction "P6_1_90") (pintype "passive"))
    )
    (net (code "66") (name "Net-(U1-P6_2)") (class "Default")
      (node (ref "PMOD1") (pin "9") (pinfunction "9_9") (pintype "passive"))
      (node (ref "U1") (pin "91") (pinfunction "P6_2_91") (pintype "passive"))
    )
    (net (code "67") (name "Net-(U1-P6_3)") (class "Default")
      (node (ref "PMOD1") (pin "10") (pinfunction "10_10") (pintype "passive"))
      (node (ref "U1") (pin "92") (pinfunction "P6_3_92") (pintype "passive"))
    )
    (net (code "68") (name "Net-(U1-P6_4)") (class "Default")
      (node (ref "PMOD3") (pin "10") (pinfunction "10_10") (pintype "passive"))
      (node (ref "U1") (pin "6") (pinfunction "P6_4_6") (pintype "passive"))
      (node (ref "U7") (pin "17") (pinfunction "RA_17") (pintype "output"))
    )
    (net (code "69") (name "Net-(U1-P6_5)") (class "Default")
      (node (ref "PMOD3") (pin "9") (pinfunction "9_9") (pintype "passive"))
      (node (ref "U1") (pin "7") (pinfunction "P6_5_7") (pintype "passive"))
      (node (ref "U7") (pin "16") (pinfunction "RB_16") (pintype "output"))
    )
    (net (code "70") (name "Net-(U1-P6_6)") (class "Default")
      (node (ref "PMOD3") (pin "8") (pinfunction "8_8") (pintype "passive"))
      (node (ref "U1") (pin "8") (pinfunction "P6_6_8") (pintype "passive"))
      (node (ref "U7") (pin "15") (pinfunction "DY_15") (pintype "input"))
    )
    (net (code "71") (name "Net-(U1-P6_7)") (class "Default")
      (node (ref "PMOD3") (pin "7") (pinfunction "7_7") (pintype "passive"))
      (node (ref "U1") (pin "9") (pinfunction "P6_7_9") (pintype "passive"))
      (node (ref "U7") (pin "14") (pinfunction "DZ/SLEW_14") (pintype "input"))
    )
    (net (code "72") (name "Net-(U1-P12_0_I2C1_SCL)") (class "Default")
      (node (ref "J5") (pin "5") (pinfunction "5_5") (pintype "passive"))
      (node (ref "R8") (pin "1") (pinfunction "1_1") (pintype "passive"))
      (node (ref "U1") (pin "53") (pinfunction "P12_0_I2C1_SCL_53") (pintype "passive"))
    )
    (net (code "73") (name "Net-(U1-P12_1_I2C1_SDA)") (class "Default")
      (node (ref "J5") (pin "3") (pinfunction "3_3") (pintype "passive"))
      (node (ref "R7") (pin "1") (pinfunction "1_1") (pintype "passive"))
      (node (ref "U1") (pin "54") (pinfunction "P12_1_I2C1_SDA_54") (pintype "passive"))
    )
    (net (code "74") (name "Net-(U1-P12_2)") (class "Default")
      (node (ref "J3") (pin "6") (pinfunction "6_6") (pintype "passive"))
      (node (ref "U1") (pin "67") (pinfunction "P12_2_67") (pintype "passive"))
    )
    (net (code "75") (name "Net-(U1-P12_3)") (class "Default")
      (node (ref "J3") (pin "8") (pinfunction "8_8") (pintype "passive"))
      (node (ref "U1") (pin "68") (pinfunction "P12_3_68") (pintype "passive"))
    )
    (net (code "76") (name "Net-(U1-P12_4_I2C0_SCL)") (class "Default")
      (node (ref "PMOD3") (pin "3") (pinfunction "3_3") (pintype "passive"))
      (node (ref "R3") (pin "2") (pinfunction "2_2") (pintype "passive"))
      (node (ref "U1") (pin "4") (pinfunction "P12_4_I2C0_SCL_4") (pintype "passive"))
    )
    (net (code "77") (name "Net-(U1-P12_5_I2C0_SDA)") (class "Default")
      (node (ref "PMOD3") (pin "4") (pinfunction "4_4") (pintype "passive"))
      (node (ref "R2") (pin "2") (pinfunction "2_2") (pintype "passive"))
      (node (ref "U1") (pin "5") (pinfunction "P12_5_I2C0_SDA_5") (pintype "passive"))
    )
    (net (code "78") (name "Net-(U1-P12_6)") (class "Default")
      (node (ref "J6") (pin "3") (pinfunction "3_3") (pintype "passive"))
      (node (ref "U1") (pin "29") (pinfunction "P12_6_29") (pintype "passive"))
    )
    (net (code "79") (name "Net-(U1-P12_7)") (class "Default")
      (node (ref "J6") (pin "1") (pinfunction "1_1") (pintype "passive"))
      (node (ref "U1") (pin "30") (pinfunction "P12_7_30") (pintype "passive"))
    )
    (net (code "80") (name "Net-(U1-P15_2_KXTLO)") (class "Default")
      (node (ref "C19") (pin "1") (pinfunction "1_1") (pintype "passive"))
      (node (ref "Q1") (pin "2") (pinfunction "2_2") (pintype "passive"))
      (node (ref "U1") (pin "55") (pinfunction "P15_2_KXTLO_55") (pintype "passive"))
    )
    (net (code "81") (name "Net-(U1-P15_3_KXTLI)") (class "Default")
      (node (ref "C20") (pin "1") (pinfunction "1_1") (pintype "passive"))
      (node (ref "Q1") (pin "1") (pinfunction "1_1") (pintype "passive"))
      (node (ref "U1") (pin "56") (pinfunction "P15_3_KXTLI_56") (pintype "passive"))
    )
    (net (code "82") (name "Net-(U1-P15_4)") (class "Default")
      (node (ref "PMOD3") (pin "1") (pinfunction "1_1") (pintype "passive"))
      (node (ref "U1") (pin "93") (pinfunction "P15_4_93") (pintype "passive"))
      (node (ref "U7") (pin "12") (pinfunction "RXEN_12") (pintype "input"))
      (node (ref "U7") (pin "13") (pinfunction "ON_13") (pintype "input"))
      (node (ref "U7") (pin "9") (pinfunction "DEN_9") (pintype "input"))
    )
    (net (code "83") (name "Net-(U1-P15_5)") (class "Default")
      (node (ref "PMOD3") (pin "2") (pinfunction "2_2") (pintype "passive"))
      (node (ref "U1") (pin "94") (pinfunction "P15_5_94") (pintype "passive"))
      (node (ref "U7") (pin "8") (pinfunction "485/~{232}_8") (pintype "input"))
    )
    (net (code "84") (name "Net-(U1-P15_6_DP)") (class "Default")
      (node (ref "R6") (pin "2") (pinfunction "2_2") (pintype "passive"))
      (node (ref "U1") (pin "35") (pinfunction "P15_6_DP_35") (pintype "passive"))
    )
    (net (code "85") (name "Net-(U1-P15_7_DM)") (class "Default")
      (node (ref "R1") (pin "2") (pinfunction "2_2") (pintype "passive"))
      (node (ref "U1") (pin "36") (pinfunction "P15_7_DM_36") (pintype "passive"))
    )
    (net (code "86") (name "Net-(U1-VCCA)") (class "Default")
      (node (ref "C13") (pin "1") (pinfunction "1_1") (pintype "passive"))
      (node (ref "U1") (pin "63") (pinfunction "VCCA_63") (pintype "passive"))
    )
    (net (code "87") (name "Net-(U1-VDDIO3)") (class "Default")
      (node (ref "C12") (pin "1") (pinfunction "1_1") (pintype "passive"))
      (node (ref "J9") (pin "2") (pinfunction "2_2") (pintype "passive"))
      (node (ref "R7") (pin "2") (pinfunction "2_2") (pintype "passive"))
      (node (ref "R8") (pin "2") (pinfunction "2_2") (pintype "passive"))
      (node (ref "U1") (pin "50") (pinfunction "VDDIO3_50") (pintype "passive"))
    )
    (net (code "88") (name "Net-(U1-~{XRES})") (class "Default")
      (node (ref "J1") (pin "10") (pinfunction "10_10") (pintype "passive"))
      (node (ref "S1") (pin "3") (pinfunction "3_3") (pintype "passive"))
      (node (ref "S1") (pin "4") (pinfunction "4_4") (pintype "passive"))
      (node (ref "U1") (pin "15") (pinfunction "~{XRES}_15") (pintype "passive"))
    )
    (net (code "89") (name "Net-(U2-OUT1)") (class "Default")
      (node (ref "J8") (pin "4") (pinfunction "4_4") (pintype "passive"))
      (node (ref "U2") (pin "6") (pinfunction "OUT2_6") (pintype "power_in"))
      (node (ref "U2") (pin "7") (pinfunction "OUT1_7") (pintype "power_in"))
    )
    (net (code "90") (name "Net-(U2-VCC1)") (class "Default")
      (node (ref "J8") (pin "5") (pinfunction "5_5") (pintype "passive"))
      (node (ref "J8") (pin "6") (pinfunction "6_6") (pintype "passive"))
      (node (ref "U2") (pin "5") (pinfunction "VCC2_5") (pintype "power_in"))
      (node (ref "U2") (pin "8") (pinfunction "VCC1_8") (pintype "power_in"))
      (node (ref "U3") (pin "5") (pinfunction "VCC2_5") (pintype "power_in"))
      (node (ref "U3") (pin "8") (pinfunction "VCC1_8") (pintype "power_in"))
      (node (ref "U4") (pin "5") (pinfunction "VCC2_5") (pintype "power_in"))
      (node (ref "U4") (pin "8") (pinfunction "VCC1_8") (pintype "power_in"))
      (node (ref "U5") (pin "5") (pinfunction "VCC2_5") (pintype "power_in"))
      (node (ref "U5") (pin "8") (pinfunction "VCC1_8") (pintype "power_in"))
    )
    (net (code "91") (name "Net-(U3-OUT1)") (class "Default")
      (node (ref "J8") (pin "3") (pinfunction "3_3") (pintype "passive"))
      (node (ref "U3") (pin "6") (pinfunction "OUT2_6") (pintype "power_in"))
      (node (ref "U3") (pin "7") (pinfunction "OUT1_7") (pintype "power_in"))
    )
    (net (code "92") (name "Net-(U4-OUT1)") (class "Default")
      (node (ref "J8") (pin "2") (pinfunction "2_2") (pintype "passive"))
      (node (ref "U4") (pin "6") (pinfunction "OUT2_6") (pintype "power_in"))
      (node (ref "U4") (pin "7") (pinfunction "OUT1_7") (pintype "power_in"))
    )
    (net (code "93") (name "Net-(U5-OUT1)") (class "Default")
      (node (ref "J8") (pin "1") (pinfunction "1_1") (pintype "passive"))
      (node (ref "U5") (pin "6") (pinfunction "OUT2_6") (pintype "power_in"))
      (node (ref "U5") (pin "7") (pinfunction "OUT1_7") (pintype "power_in"))
    )
    (net (code "94") (name "Net-(U7-A)") (class "Default")
      (node (ref "U7") (pin "4") (pinfunction "A_4") (pintype "input"))
      (node (ref "X2") (pin "2") (pinfunction "2_2") (pintype "passive"))
    )
    (net (code "95") (name "Net-(U7-B)") (class "Default")
      (node (ref "U7") (pin "5") (pinfunction "B_5") (pintype "input"))
      (node (ref "X2") (pin "8") (pinfunction "8_8") (pintype "passive"))
    )
    (net (code "96") (name "Net-(U7-C1+)") (class "Default")
      (node (ref "C3") (pin "1") (pinfunction "1_1") (pintype "passive"))
      (node (ref "U7") (pin "1") (pinfunction "C1+_1") (pintype "passive"))
    )
    (net (code "97") (name "Net-(U7-C1-)") (class "Default")
      (node (ref "C3") (pin "2") (pinfunction "2_2") (pintype "passive"))
      (node (ref "U7") (pin "2") (pinfunction "C1-_2") (pintype "passive"))
    )
    (net (code "98") (name "Net-(U7-C2+)") (class "Default")
      (node (ref "C4") (pin "1") (pinfunction "1_1") (pintype "passive"))
      (node (ref "U7") (pin "20") (pinfunction "C2+_20") (pintype "passive"))
    )
    (net (code "99") (name "Net-(U7-C2-)") (class "Default")
      (node (ref "C4") (pin "2") (pinfunction "2_2") (pintype "passive"))
      (node (ref "U7") (pin "19") (pinfunction "C2-_19") (pintype "passive"))
    )
    (net (code "100") (name "Net-(U7-V+)") (class "Default")
      (node (ref "C6") (pin "1") (pinfunction "1_1") (pintype "passive"))
      (node (ref "U7") (pin "3") (pinfunction "V+_3") (pintype "power_in"))
    )
    (net (code "101") (name "Net-(U7-V-)") (class "Default")
      (node (ref "C5") (pin "1") (pinfunction "1_1") (pintype "passive"))
      (node (ref "U7") (pin "11") (pinfunction "V-_11") (pintype "power_in"))
    )
    (net (code "102") (name "Net-(U7-Y)") (class "Default")
      (node (ref "U7") (pin "6") (pinfunction "Y_6") (pintype "output"))
      (node (ref "X2") (pin "3") (pinfunction "3_3") (pintype "passive"))
    )
    (net (code "103") (name "Net-(U7-Z)") (class "Default")
      (node (ref "U7") (pin "7") (pinfunction "Z_7") (pintype "output"))
      (node (ref "X2") (pin "7") (pinfunction "7_7") (pintype "passive"))
    )
    (net (code "104") (name "unconnected-(J5-Pad1)") (class "Default")
      (node (ref "J5") (pin "1") (pinfunction "1_1") (pintype "passive"))
    )
    (net (code "105") (name "unconnected-(J5-Pad11)") (class "Default")
      (node (ref "J5") (pin "11") (pinfunction "11_11") (pintype "passive"))
    )
    (net (code "106") (name "unconnected-(J5-Pad12)") (class "Default")
      (node (ref "J5") (pin "12") (pinfunction "12_12") (pintype "passive"))
    )
    (net (code "107") (name "unconnected-(J5-Pad13)") (class "Default")
      (node (ref "J5") (pin "13") (pinfunction "13_13") (pintype "passive"))
    )
    (net (code "108") (name "unconnected-(J5-Pad15)") (class "Default")
      (node (ref "J5") (pin "15") (pinfunction "15_15") (pintype "passive"))
    )
    (net (code "109") (name "unconnected-(J5-Pad16)") (class "Default")
      (node (ref "J5") (pin "16") (pinfunction "16_16") (pintype "passive"))
    )
    (net (code "110") (name "unconnected-(J5-Pad17)") (class "Default")
      (node (ref "J5") (pin "17") (pinfunction "17_17") (pintype "passive"))
    )
    (net (code "111") (name "unconnected-(J5-Pad18)") (class "Default")
      (node (ref "J5") (pin "18") (pinfunction "18_18") (pintype "passive"))
    )
    (net (code "112") (name "unconnected-(U1-NC-Pad11)") (class "Default")
      (node (ref "U1") (pin "11") (pinfunction "NC_11") (pintype "passive"))
    )
    (net (code "113") (name "unconnected-(U1-NC-Pad40)") (class "Default")
      (node (ref "U1") (pin "40") (pinfunction "NC_40") (pintype "passive"))
    )
    (net (code "114") (name "unconnected-(U1-NC-Pad41)") (class "Default")
      (node (ref "U1") (pin "41") (pinfunction "NC_41") (pintype "passive"))
    )
    (net (code "115") (name "unconnected-(U1-NC-Pad57)") (class "Default")
      (node (ref "U1") (pin "57") (pinfunction "NC_57") (pintype "passive"))
    )
    (net (code "116") (name "unconnected-(U1-NC-Pad58)") (class "Default")
      (node (ref "U1") (pin "58") (pinfunction "NC_58") (pintype "passive"))
    )
    (net (code "117") (name "unconnected-(U1-NC-Pad59)") (class "Default")
      (node (ref "U1") (pin "59") (pinfunction "NC_59") (pintype "passive"))
    )
    (net (code "118") (name "unconnected-(U1-NC-Pad60)") (class "Default")
      (node (ref "U1") (pin "60") (pinfunction "NC_60") (pintype "passive"))
    )
    (net (code "119") (name "unconnected-(U1-NC-Pad61)") (class "Default")
      (node (ref "U1") (pin "61") (pinfunction "NC_61") (pintype "passive"))
    )
    (net (code "120") (name "unconnected-(U1-NC-Pad62)") (class "Default")
      (node (ref "U1") (pin "62") (pinfunction "NC_62") (pintype "passive"))
    )
    (net (code "121") (name "unconnected-(U1-P1_5_NTRST-Pad25)") (class "Default")
      (node (ref "U1") (pin "25") (pinfunction "P1_5_NTRST_25") (pintype "passive"))
    )
    (net (code "122") (name "unconnected-(U1-P15_0_MXTLO-Pad42)") (class "Default")
      (node (ref "U1") (pin "42") (pinfunction "P15_0_MXTLO_42") (pintype "passive"))
    )
    (net (code "123") (name "unconnected-(U1-P15_1_MXTLI-Pad43)") (class "Default")
      (node (ref "U1") (pin "43") (pinfunction "P15_1_MXTLI_43") (pintype "passive"))
    )
    (net (code "124") (name "unconnected-(U2-STAT-Pad3)") (class "Default")
      (node (ref "U2") (pin "3") (pinfunction "STAT_3") (pintype "output"))
    )
    (net (code "125") (name "unconnected-(U2-S_DIS-Pad4)") (class "Default")
      (node (ref "U2") (pin "4") (pinfunction "S_DIS_4") (pintype "input"))
    )
    (net (code "126") (name "unconnected-(U3-STAT-Pad3)") (class "Default")
      (node (ref "U3") (pin "3") (pinfunction "STAT_3") (pintype "output"))
    )
    (net (code "127") (name "unconnected-(U3-S_DIS-Pad4)") (class "Default")
      (node (ref "U3") (pin "4") (pinfunction "S_DIS_4") (pintype "input"))
    )
    (net (code "128") (name "unconnected-(U4-STAT-Pad3)") (class "Default")
      (node (ref "U4") (pin "3") (pinfunction "STAT_3") (pintype "output"))
    )
    (net (code "129") (name "unconnected-(U4-S_DIS-Pad4)") (class "Default")
      (node (ref "U4") (pin "4") (pinfunction "S_DIS_4") (pintype "input"))
    )
    (net (code "130") (name "unconnected-(U5-STAT-Pad3)") (class "Default")
      (node (ref "U5") (pin "3") (pinfunction "STAT_3") (pintype "output"))
    )
    (net (code "131") (name "unconnected-(U5-S_DIS-Pad4)") (class "Default")
      (node (ref "U5") (pin "4") (pinfunction "S_DIS_4") (pintype "input"))
    )
    (net (code "132") (name "unconnected-(X2-Pad1)") (class "Default")
      (node (ref "X2") (pin "1") (pinfunction "1_1") (pintype "passive"))
    )
    (net (code "133") (name "unconnected-(X2-Pad4)") (class "Default")
      (node (ref "X2") (pin "4") (pinfunction "4_4") (pintype "passive"))
    )
    (net (code "134") (name "unconnected-(X2-Pad6)") (class "Default")
      (node (ref "X2") (pin "6") (pinfunction "6_6") (pintype "passive"))
    )
    (net (code "135") (name "unconnected-(X2-Pad9)") (class "Default")
      (node (ref "X2") (pin "9") (pinfunction "9_9") (pintype "passive"))
    )
  )
)
